# sch.net
KiCad netlist of a schematic drawn in Altium Designer
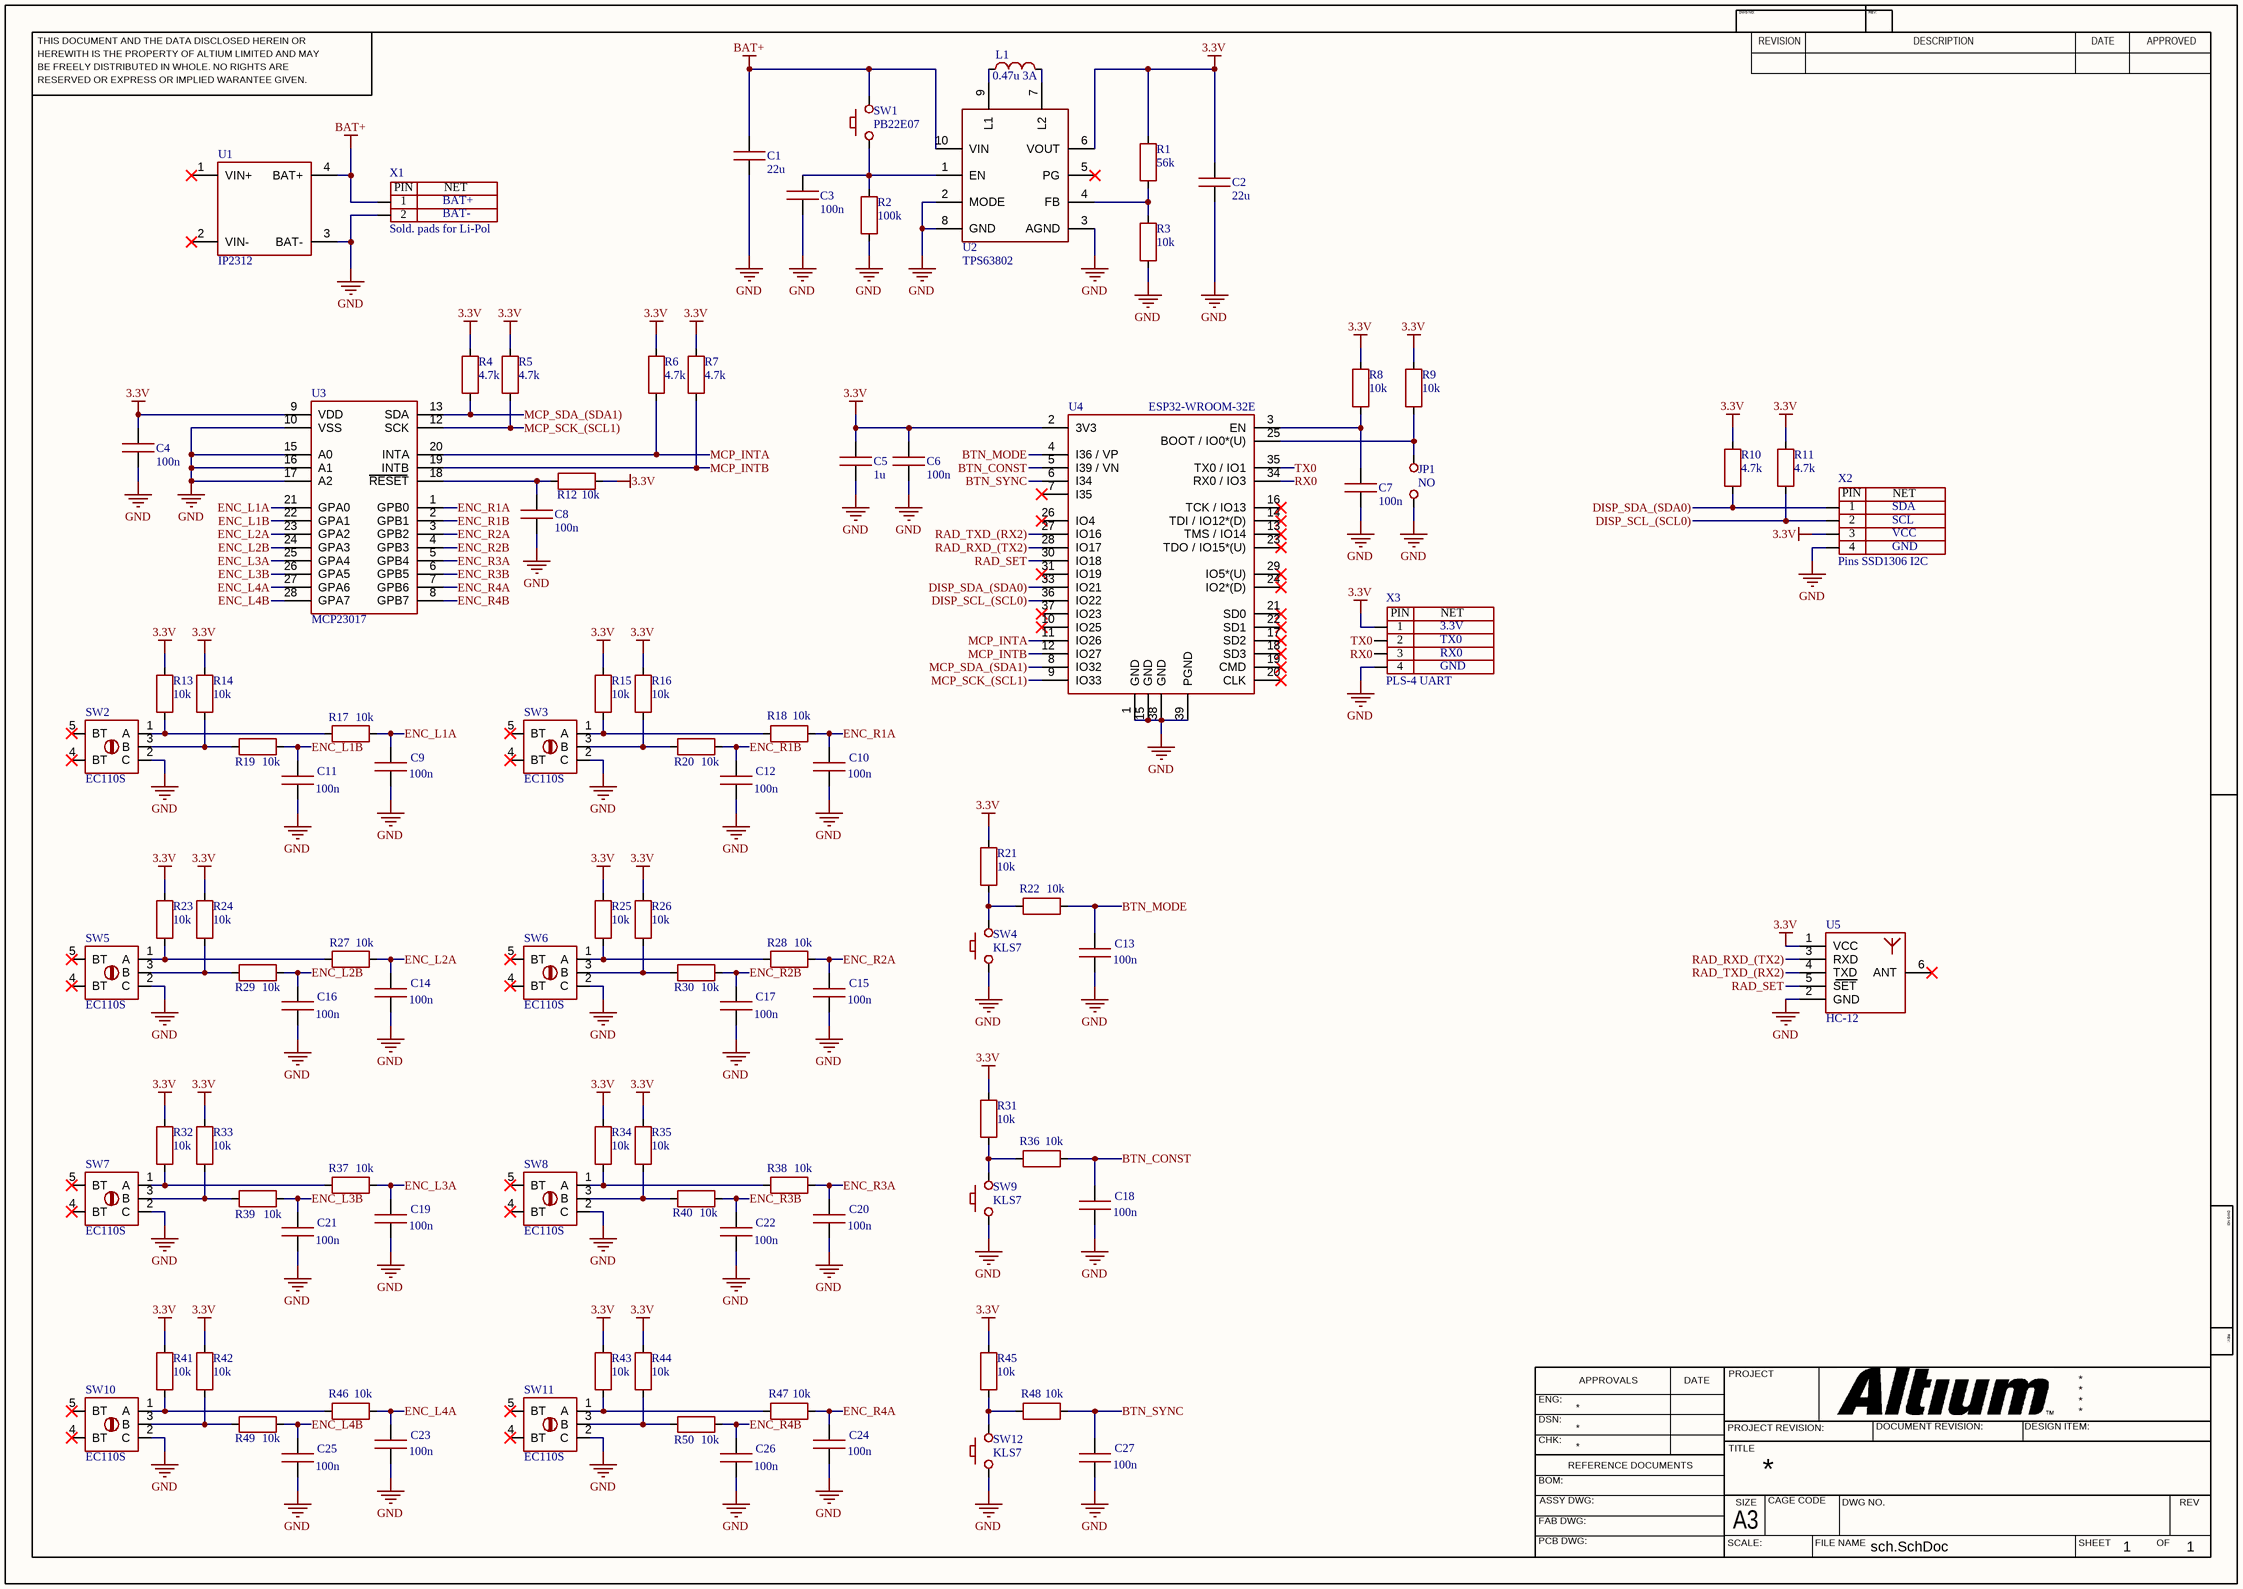
[diagram p0: sch.SchDoc]

(export (version "E")
  (design (tool "Eeschema 10.0.6"))
  (components
    (comp (ref "C1")
      (value "22u")
      (footprint "C1210")
      (description "22 мкФ X7R 10% 25В 1210, GRM32ER71E226KE15L")
      (libsource (lib "LeeSch") (part "Capacitor"))
    )
    (comp (ref "C2")
      (value "22u")
      (footprint "C1210")
      (description "22 мкФ X7R 10% 25В 1210, GRM32ER71E226KE15L")
      (libsource (lib "LeeSch") (part "Capacitor"))
    )
    (comp (ref "C3")
      (value "100n")
      (footprint "C0402")
      (description "0.1 мкФ X7R 25В 10% 0402, GRM155R71E104KE14D")
      (libsource (lib "LeeSch") (part "Capacitor"))
    )
    (comp (ref "C4")
      (value "100n")
      (footprint "C0402")
      (description "0.1 мкФ X7R 25В 10% 0402, GRM155R71E104KE14D")
      (libsource (lib "LeeSch") (part "Capacitor"))
    )
    (comp (ref "C5")
      (value "1u")
      (footprint "C0603")
      (description "1 мкФ X7R 25В 10% 0603, GCM188R71E105KA64D")
      (libsource (lib "LeeSch") (part "Capacitor"))
    )
    (comp (ref "C6")
      (value "100n")
      (footprint "C0402")
      (description "0.1 мкФ X7R 25В 10% 0402, GRM155R71E104KE14D")
      (libsource (lib "LeeSch") (part "Capacitor"))
    )
    (comp (ref "C7")
      (value "100n")
      (footprint "C0402")
      (description "0.1 мкФ X7R 25В 10% 0402, GRM155R71E104KE14D")
      (libsource (lib "LeeSch") (part "Capacitor"))
    )
    (comp (ref "C8")
      (value "100n")
      (footprint "C0402")
      (description "0.1 мкФ X7R 25В 10% 0402, GRM155R71E104KE14D")
      (libsource (lib "LeeSch") (part "Capacitor"))
    )
    (comp (ref "C9")
      (value "100n")
      (footprint "C0402")
      (description "0.1 мкФ X7R 25В 10% 0402, GRM155R71E104KE14D")
      (libsource (lib "LeeSch") (part "Capacitor"))
    )
    (comp (ref "C10")
      (value "100n")
      (footprint "C0402")
      (description "0.1 мкФ X7R 25В 10% 0402, GRM155R71E104KE14D")
      (libsource (lib "LeeSch") (part "Capacitor"))
    )
    (comp (ref "C11")
      (value "100n")
      (footprint "C0402")
      (description "0.1 мкФ X7R 25В 10% 0402, GRM155R71E104KE14D")
      (libsource (lib "LeeSch") (part "Capacitor"))
    )
    (comp (ref "C12")
      (value "100n")
      (footprint "C0402")
      (description "0.1 мкФ X7R 25В 10% 0402, GRM155R71E104KE14D")
      (libsource (lib "LeeSch") (part "Capacitor"))
    )
    (comp (ref "C13")
      (value "100n")
      (footprint "C0402")
      (description "0.1 мкФ X7R 25В 10% 0402, GRM155R71E104KE14D")
      (libsource (lib "LeeSch") (part "Capacitor"))
    )
    (comp (ref "C14")
      (value "100n")
      (footprint "C0402")
      (description "0.1 мкФ X7R 25В 10% 0402, GRM155R71E104KE14D")
      (libsource (lib "LeeSch") (part "Capacitor"))
    )
    (comp (ref "C15")
      (value "100n")
      (footprint "C0402")
      (description "0.1 мкФ X7R 25В 10% 0402, GRM155R71E104KE14D")
      (libsource (lib "LeeSch") (part "Capacitor"))
    )
    (comp (ref "C16")
      (value "100n")
      (footprint "C0402")
      (description "0.1 мкФ X7R 25В 10% 0402, GRM155R71E104KE14D")
      (libsource (lib "LeeSch") (part "Capacitor"))
    )
    (comp (ref "C17")
      (value "100n")
      (footprint "C0402")
      (description "0.1 мкФ X7R 25В 10% 0402, GRM155R71E104KE14D")
      (libsource (lib "LeeSch") (part "Capacitor"))
    )
    (comp (ref "C18")
      (value "100n")
      (footprint "C0402")
      (description "0.1 мкФ X7R 25В 10% 0402, GRM155R71E104KE14D")
      (libsource (lib "LeeSch") (part "Capacitor"))
    )
    (comp (ref "C19")
      (value "100n")
      (footprint "C0402")
      (description "0.1 мкФ X7R 25В 10% 0402, GRM155R71E104KE14D")
      (libsource (lib "LeeSch") (part "Capacitor"))
    )
    (comp (ref "C20")
      (value "100n")
      (footprint "C0402")
      (description "0.1 мкФ X7R 25В 10% 0402, GRM155R71E104KE14D")
      (libsource (lib "LeeSch") (part "Capacitor"))
    )
    (comp (ref "C21")
      (value "100n")
      (footprint "C0402")
      (description "0.1 мкФ X7R 25В 10% 0402, GRM155R71E104KE14D")
      (libsource (lib "LeeSch") (part "Capacitor"))
    )
    (comp (ref "C22")
      (value "100n")
      (footprint "C0402")
      (description "0.1 мкФ X7R 25В 10% 0402, GRM155R71E104KE14D")
      (libsource (lib "LeeSch") (part "Capacitor"))
    )
    (comp (ref "C23")
      (value "100n")
      (footprint "C0402")
      (description "0.1 мкФ X7R 25В 10% 0402, GRM155R71E104KE14D")
      (libsource (lib "LeeSch") (part "Capacitor"))
    )
    (comp (ref "C24")
      (value "100n")
      (footprint "C0402")
      (description "0.1 мкФ X7R 25В 10% 0402, GRM155R71E104KE14D")
      (libsource (lib "LeeSch") (part "Capacitor"))
    )
    (comp (ref "C25")
      (value "100n")
      (footprint "C0402")
      (description "0.1 мкФ X7R 25В 10% 0402, GRM155R71E104KE14D")
      (libsource (lib "LeeSch") (part "Capacitor"))
    )
    (comp (ref "C26")
      (value "100n")
      (footprint "C0402")
      (description "0.1 мкФ X7R 25В 10% 0402, GRM155R71E104KE14D")
      (libsource (lib "LeeSch") (part "Capacitor"))
    )
    (comp (ref "C27")
      (value "100n")
      (footprint "C0402")
      (description "0.1 мкФ X7R 25В 10% 0402, GRM155R71E104KE14D")
      (libsource (lib "LeeSch") (part "Capacitor"))
    )
    (comp (ref "JP1")
      (value "NO")
      (footprint "jumper 3mm")
      (libsource (lib "LeeSch") (part "Jumper (Normal Open)"))
    )
    (comp (ref "L1")
      (value "0.47u 3A")
      (footprint "INDUCTOR 2x1.6mm VLS-CX")
      (description "VLS201610CX-R47M-1, 0.47мкГн, 3.16А")
      (libsource (lib "LeeSch") (part "Inductance"))
    )
    (comp (ref "R1")
      (value "56k")
      (footprint "R0402")
      (description "0402")
      (libsource (lib "") (part "Resistor_2"))
    )
    (comp (ref "R2")
      (value "100k")
      (footprint "R0402")
      (description "0402")
      (libsource (lib "") (part "Resistor_2"))
    )
    (comp (ref "R3")
      (value "10k")
      (footprint "R0402")
      (description "0402")
      (libsource (lib "") (part "Resistor_2"))
    )
    (comp (ref "R4")
      (value "4.7k")
      (footprint "R0402")
      (description "0402")
      (libsource (lib "") (part "Resistor_2"))
    )
    (comp (ref "R5")
      (value "4.7k")
      (footprint "R0402")
      (description "0402")
      (libsource (lib "") (part "Resistor_2"))
    )
    (comp (ref "R6")
      (value "4.7k")
      (footprint "R0402")
      (description "0402")
      (libsource (lib "") (part "Resistor_2"))
    )
    (comp (ref "R7")
      (value "4.7k")
      (footprint "R0402")
      (description "0402")
      (libsource (lib "") (part "Resistor_2"))
    )
    (comp (ref "R8")
      (value "10k")
      (footprint "R0402")
      (description "0402")
      (libsource (lib "") (part "Resistor_2"))
    )
    (comp (ref "R9")
      (value "10k")
      (footprint "R0402")
      (description "0402")
      (libsource (lib "") (part "Resistor_2"))
    )
    (comp (ref "R10")
      (value "4.7k")
      (footprint "R0402")
      (description "0402")
      (libsource (lib "") (part "Resistor_2"))
    )
    (comp (ref "R11")
      (value "4.7k")
      (footprint "R0402")
      (description "0402")
      (libsource (lib "") (part "Resistor_2"))
    )
    (comp (ref "R12")
      (value "10k")
      (footprint "R0402")
      (description "0402")
      (libsource (lib "LeeSch") (part "Resistor"))
    )
    (comp (ref "R13")
      (value "10k")
      (footprint "R0402")
      (description "0402")
      (libsource (lib "LeeSch") (part "Resistor"))
    )
    (comp (ref "R14")
      (value "10k")
      (footprint "R0402")
      (description "0402")
      (libsource (lib "LeeSch") (part "Resistor"))
    )
    (comp (ref "R15")
      (value "10k")
      (footprint "R0402")
      (description "0402")
      (libsource (lib "LeeSch") (part "Resistor"))
    )
    (comp (ref "R16")
      (value "10k")
      (footprint "R0402")
      (description "0402")
      (libsource (lib "LeeSch") (part "Resistor"))
    )
    (comp (ref "R17")
      (value "10k")
      (footprint "R0402")
      (description "0402")
      (libsource (lib "") (part "Resistor_1"))
    )
    (comp (ref "R18")
      (value "10k")
      (footprint "R0402")
      (description "0402")
      (libsource (lib "") (part "Resistor_1"))
    )
    (comp (ref "R19")
      (value "10k")
      (footprint "R0402")
      (description "0402")
      (libsource (lib "") (part "Resistor_1"))
    )
    (comp (ref "R20")
      (value "10k")
      (footprint "R0402")
      (description "0402")
      (libsource (lib "") (part "Resistor_1"))
    )
    (comp (ref "R21")
      (value "10k")
      (footprint "R0402")
      (description "0402")
      (libsource (lib "") (part "Resistor_2"))
    )
    (comp (ref "R22")
      (value "10k")
      (footprint "R0402")
      (description "0402")
      (libsource (lib "") (part "Resistor_1"))
    )
    (comp (ref "R23")
      (value "10k")
      (footprint "R0402")
      (description "0402")
      (libsource (lib "LeeSch") (part "Resistor"))
    )
    (comp (ref "R24")
      (value "10k")
      (footprint "R0402")
      (description "0402")
      (libsource (lib "LeeSch") (part "Resistor"))
    )
    (comp (ref "R25")
      (value "10k")
      (footprint "R0402")
      (description "0402")
      (libsource (lib "LeeSch") (part "Resistor"))
    )
    (comp (ref "R26")
      (value "10k")
      (footprint "R0402")
      (description "0402")
      (libsource (lib "LeeSch") (part "Resistor"))
    )
    (comp (ref "R27")
      (value "10k")
      (footprint "R0402")
      (description "0402")
      (libsource (lib "") (part "Resistor_1"))
    )
    (comp (ref "R28")
      (value "10k")
      (footprint "R0402")
      (description "0402")
      (libsource (lib "") (part "Resistor_1"))
    )
    (comp (ref "R29")
      (value "10k")
      (footprint "R0402")
      (description "0402")
      (libsource (lib "") (part "Resistor_1"))
    )
    (comp (ref "R30")
      (value "10k")
      (footprint "R0402")
      (description "0402")
      (libsource (lib "") (part "Resistor_1"))
    )
    (comp (ref "R31")
      (value "10k")
      (footprint "R0402")
      (description "0402")
      (libsource (lib "") (part "Resistor_2"))
    )
    (comp (ref "R32")
      (value "10k")
      (footprint "R0402")
      (description "0402")
      (libsource (lib "LeeSch") (part "Resistor"))
    )
    (comp (ref "R33")
      (value "10k")
      (footprint "R0402")
      (description "0402")
      (libsource (lib "LeeSch") (part "Resistor"))
    )
    (comp (ref "R34")
      (value "10k")
      (footprint "R0402")
      (description "0402")
      (libsource (lib "LeeSch") (part "Resistor"))
    )
    (comp (ref "R35")
      (value "10k")
      (footprint "R0402")
      (description "0402")
      (libsource (lib "LeeSch") (part "Resistor"))
    )
    (comp (ref "R36")
      (value "10k")
      (footprint "R0402")
      (description "0402")
      (libsource (lib "") (part "Resistor_1"))
    )
    (comp (ref "R37")
      (value "10k")
      (footprint "R0402")
      (description "0402")
      (libsource (lib "") (part "Resistor_1"))
    )
    (comp (ref "R38")
      (value "10k")
      (footprint "R0402")
      (description "0402")
      (libsource (lib "") (part "Resistor_1"))
    )
    (comp (ref "R39")
      (value "10k")
      (footprint "R0402")
      (description "0402")
      (libsource (lib "") (part "Resistor_1"))
    )
    (comp (ref "R40")
      (value "10k")
      (footprint "R0402")
      (description "0402")
      (libsource (lib "") (part "Resistor_1"))
    )
    (comp (ref "R41")
      (value "10k")
      (footprint "R0402")
      (description "0402")
      (libsource (lib "LeeSch") (part "Resistor"))
    )
    (comp (ref "R42")
      (value "10k")
      (footprint "R0402")
      (description "0402")
      (libsource (lib "LeeSch") (part "Resistor"))
    )
    (comp (ref "R43")
      (value "10k")
      (footprint "R0402")
      (description "0402")
      (libsource (lib "LeeSch") (part "Resistor"))
    )
    (comp (ref "R44")
      (value "10k")
      (footprint "R0402")
      (description "0402")
      (libsource (lib "LeeSch") (part "Resistor"))
    )
    (comp (ref "R45")
      (value "10k")
      (footprint "R0402")
      (description "0402")
      (libsource (lib "") (part "Resistor_2"))
    )
    (comp (ref "R46")
      (value "10k")
      (footprint "R0402")
      (description "0402")
      (libsource (lib "") (part "Resistor_1"))
    )
    (comp (ref "R47")
      (value "10k")
      (footprint "R0402")
      (description "0402")
      (libsource (lib "") (part "Resistor_1"))
    )
    (comp (ref "R48")
      (value "10k")
      (footprint "R0402")
      (description "0402")
      (libsource (lib "") (part "Resistor_1"))
    )
    (comp (ref "R49")
      (value "10k")
      (footprint "R0402")
      (description "0402")
      (libsource (lib "") (part "Resistor_1"))
    )
    (comp (ref "R50")
      (value "10k")
      (footprint "R0402")
      (description "0402")
      (libsource (lib "") (part "Resistor_1"))
    )
    (comp (ref "SW1")
      (value "PB22E07")
      (footprint "PB22E07 7х7х12")
      (description "PB22E07 с фиксацией 7x7x12 mm")
      (libsource (lib "LeeSch") (part "Switch Button (Normal Open)"))
    )
    (comp (ref "SW2")
      (value "EC110S")
      (footprint "EC110S(ЭНКОДЕР)")
      (description "Incremental Encoder with button\r\nEC110S 20/20 10mm")
      (libsource (lib "LeeSch") (part "Encoder (Incremental, with Button)"))
    )
    (comp (ref "SW3")
      (value "EC110S")
      (footprint "EC110S(ЭНКОДЕР)")
      (description "Incremental Encoder with button\r\nEC110S 20/20 10mm")
      (libsource (lib "LeeSch") (part "Encoder (Incremental, with Button)"))
    )
    (comp (ref "SW4")
      (value "KLS7")
      (footprint "SMT Tactile Switch (6mm x 6mm)")
      (description "KLS7-TS6604-4.3-180 (IT-1102S) 6х6х4.3мм")
      (libsource (lib "LeeSch") (part "Switch Button (Normal Open)"))
    )
    (comp (ref "SW5")
      (value "EC110S")
      (footprint "EC110S(ЭНКОДЕР)")
      (description "Incremental Encoder with button\r\nEC110S 20/20 10mm")
      (libsource (lib "LeeSch") (part "Encoder (Incremental, with Button)"))
    )
    (comp (ref "SW6")
      (value "EC110S")
      (footprint "EC110S(ЭНКОДЕР)")
      (description "Incremental Encoder with button\r\nEC110S 20/20 10mm")
      (libsource (lib "LeeSch") (part "Encoder (Incremental, with Button)"))
    )
    (comp (ref "SW7")
      (value "EC110S")
      (footprint "EC110S(ЭНКОДЕР)")
      (description "Incremental Encoder with button\r\nEC110S 20/20 10mm")
      (libsource (lib "LeeSch") (part "Encoder (Incremental, with Button)"))
    )
    (comp (ref "SW8")
      (value "EC110S")
      (footprint "EC110S(ЭНКОДЕР)")
      (description "Incremental Encoder with button\r\nEC110S 20/20 10mm")
      (libsource (lib "LeeSch") (part "Encoder (Incremental, with Button)"))
    )
    (comp (ref "SW9")
      (value "KLS7")
      (footprint "SMT Tactile Switch (6mm x 6mm)")
      (description "KLS7-TS6604-4.3-180 (IT-1102S) 6х6х4.3мм")
      (libsource (lib "LeeSch") (part "Switch Button (Normal Open)"))
    )
    (comp (ref "SW10")
      (value "EC110S")
      (footprint "EC110S(ЭНКОДЕР)")
      (description "Incremental Encoder with button\r\nEC110S 20/20 10mm")
      (libsource (lib "LeeSch") (part "Encoder (Incremental, with Button)"))
    )
    (comp (ref "SW11")
      (value "EC110S")
      (footprint "EC110S(ЭНКОДЕР)")
      (description "Incremental Encoder with button\r\nEC110S 20/20 10mm")
      (libsource (lib "LeeSch") (part "Encoder (Incremental, with Button)"))
    )
    (comp (ref "SW12")
      (value "KLS7")
      (footprint "SMT Tactile Switch (6mm x 6mm)")
      (description "KLS7-TS6604-4.3-180 (IT-1102S) 6х6х4.3мм")
      (libsource (lib "LeeSch") (part "Switch Button (Normal Open)"))
    )
    (comp (ref "U1")
      (value "IP2312")
      (footprint "IP2312 Modul")
      (description "Impulse charger without protection")
      (libsource (lib "LeeSch") (part "MOD_Charger_IP2312"))
    )
    (comp (ref "U2")
      (value "TPS63802")
      (footprint "VSON-HR-10(3x2)")
      (description "Integral Buck-Boost Regulator 2A out")
      (libsource (lib "LeeSch") (part "IC_ImpRegulator_TPS63802"))
    )
    (comp (ref "U3")
      (value "MCP23017")
      (footprint "SSOP-28N")
      (description "16-Bit I/O Expander with Serial Interface")
      (libsource (lib "LeeSch") (part "IC_PortsExp_MCP23017"))
    )
    (comp (ref "U4")
      (value "ESP32-WROOM-32E")
      (footprint "ESP32­WROOM­32E")
      (libsource (lib "LeeSch") (part "MOD_ESP32-WROOM-32"))
    )
    (comp (ref "U5")
      (value "HC-12")
      (footprint "HC-12(Модуль)")
      (description "Radio module 433MHz UART Interface")
      (libsource (lib "LeeSch") (part "MOD_RadioMod_HC-12"))
    )
    (comp (ref "X1")
      (value "Sold. pads for Li-Pol")
      (footprint "CWF-2R (DS1069-2 MR)")
      (libsource (lib "LeeSch") (part "Terminal block (2-pin)"))
    )
    (comp (ref "X2")
      (value "Pins SSD1306 I2C")
      (footprint "SSD1306 27.5x27.8 NO GABARIT")
      (libsource (lib "LeeSch") (part "Terminal block (4-pin)"))
    )
    (comp (ref "X3")
      (value "PLS-4 UART")
      (footprint "PLS-4")
      (libsource (lib "LeeSch") (part "Terminal block (4-pin)"))
    )
  )
  (nets
    (net (code "1") (name "/BTN_CONST") (class "Default")
      (node (ref "C18") (pin "2") (pinfunction "2_2") (pintype "passive"))
      (node (ref "R36") (pin "1") (pinfunction "1_1") (pintype "passive"))
      (node (ref "U4") (pin "5") (pinfunction "I39_/_VN_5") (pintype "passive"))
    )
    (net (code "2") (name "/BTN_MODE") (class "Default")
      (node (ref "C13") (pin "2") (pinfunction "2_2") (pintype "passive"))
      (node (ref "R22") (pin "1") (pinfunction "1_1") (pintype "passive"))
      (node (ref "U4") (pin "4") (pinfunction "I36_/_VP_4") (pintype "passive"))
    )
    (net (code "3") (name "/BTN_SYNC") (class "Default")
      (node (ref "C27") (pin "2") (pinfunction "2_2") (pintype "passive"))
      (node (ref "R48") (pin "1") (pinfunction "1_1") (pintype "passive"))
      (node (ref "U4") (pin "6") (pinfunction "I34_6") (pintype "passive"))
    )
    (net (code "4") (name "/DISP_SCL_(SCL0)") (class "Default")
      (node (ref "R11") (pin "1") (pinfunction "1_1") (pintype "passive"))
      (node (ref "U4") (pin "36") (pinfunction "IO22_36") (pintype "passive"))
      (node (ref "X2") (pin "2") (pinfunction "NET2_2") (pintype "passive"))
    )
    (net (code "5") (name "/DISP_SDA_(SDA0)") (class "Default")
      (node (ref "R10") (pin "1") (pinfunction "1_1") (pintype "passive"))
      (node (ref "U4") (pin "33") (pinfunction "IO21_33") (pintype "passive"))
      (node (ref "X2") (pin "1") (pinfunction "NET1_1") (pintype "passive"))
    )
    (net (code "6") (name "/ENC_L1A") (class "Default")
      (node (ref "C9") (pin "2") (pinfunction "2_2") (pintype "passive"))
      (node (ref "R17") (pin "1") (pinfunction "1_1") (pintype "passive"))
      (node (ref "U3") (pin "21") (pinfunction "GPA0_21") (pintype "passive"))
    )
    (net (code "7") (name "/ENC_L1B") (class "Default")
      (node (ref "C11") (pin "2") (pinfunction "2_2") (pintype "passive"))
      (node (ref "R19") (pin "1") (pinfunction "1_1") (pintype "passive"))
      (node (ref "U3") (pin "22") (pinfunction "GPA1_22") (pintype "passive"))
    )
    (net (code "8") (name "/ENC_L2A") (class "Default")
      (node (ref "C14") (pin "2") (pinfunction "2_2") (pintype "passive"))
      (node (ref "R27") (pin "1") (pinfunction "1_1") (pintype "passive"))
      (node (ref "U3") (pin "23") (pinfunction "GPA2_23") (pintype "passive"))
    )
    (net (code "9") (name "/ENC_L2B") (class "Default")
      (node (ref "C16") (pin "2") (pinfunction "2_2") (pintype "passive"))
      (node (ref "R29") (pin "1") (pinfunction "1_1") (pintype "passive"))
      (node (ref "U3") (pin "24") (pinfunction "GPA3_24") (pintype "passive"))
    )
    (net (code "10") (name "/ENC_L3A") (class "Default")
      (node (ref "C19") (pin "2") (pinfunction "2_2") (pintype "passive"))
      (node (ref "R37") (pin "1") (pinfunction "1_1") (pintype "passive"))
      (node (ref "U3") (pin "25") (pinfunction "GPA4_25") (pintype "passive"))
    )
    (net (code "11") (name "/ENC_L3B") (class "Default")
      (node (ref "C21") (pin "2") (pinfunction "2_2") (pintype "passive"))
      (node (ref "R39") (pin "1") (pinfunction "1_1") (pintype "passive"))
      (node (ref "U3") (pin "26") (pinfunction "GPA5_26") (pintype "passive"))
    )
    (net (code "12") (name "/ENC_L4A") (class "Default")
      (node (ref "C23") (pin "2") (pinfunction "2_2") (pintype "passive"))
      (node (ref "R46") (pin "1") (pinfunction "1_1") (pintype "passive"))
      (node (ref "U3") (pin "27") (pinfunction "GPA6_27") (pintype "passive"))
    )
    (net (code "13") (name "/ENC_L4B") (class "Default")
      (node (ref "C25") (pin "2") (pinfunction "2_2") (pintype "passive"))
      (node (ref "R49") (pin "1") (pinfunction "1_1") (pintype "passive"))
      (node (ref "U3") (pin "28") (pinfunction "GPA7_28") (pintype "passive"))
    )
    (net (code "14") (name "/ENC_R1A") (class "Default")
      (node (ref "C10") (pin "2") (pinfunction "2_2") (pintype "passive"))
      (node (ref "R18") (pin "1") (pinfunction "1_1") (pintype "passive"))
      (node (ref "U3") (pin "1") (pinfunction "GPB0_1") (pintype "passive"))
    )
    (net (code "15") (name "/ENC_R1B") (class "Default")
      (node (ref "C12") (pin "2") (pinfunction "2_2") (pintype "passive"))
      (node (ref "R20") (pin "1") (pinfunction "1_1") (pintype "passive"))
      (node (ref "U3") (pin "2") (pinfunction "GPB1_2") (pintype "passive"))
    )
    (net (code "16") (name "/ENC_R2A") (class "Default")
      (node (ref "C15") (pin "2") (pinfunction "2_2") (pintype "passive"))
      (node (ref "R28") (pin "1") (pinfunction "1_1") (pintype "passive"))
      (node (ref "U3") (pin "3") (pinfunction "GPB2_3") (pintype "passive"))
    )
    (net (code "17") (name "/ENC_R2B") (class "Default")
      (node (ref "C17") (pin "2") (pinfunction "2_2") (pintype "passive"))
      (node (ref "R30") (pin "1") (pinfunction "1_1") (pintype "passive"))
      (node (ref "U3") (pin "4") (pinfunction "GPB3_4") (pintype "passive"))
    )
    (net (code "18") (name "/ENC_R3A") (class "Default")
      (node (ref "C20") (pin "2") (pinfunction "2_2") (pintype "passive"))
      (node (ref "R38") (pin "1") (pinfunction "1_1") (pintype "passive"))
      (node (ref "U3") (pin "5") (pinfunction "GPB4_5") (pintype "passive"))
    )
    (net (code "19") (name "/ENC_R3B") (class "Default")
      (node (ref "C22") (pin "2") (pinfunction "2_2") (pintype "passive"))
      (node (ref "R40") (pin "1") (pinfunction "1_1") (pintype "passive"))
      (node (ref "U3") (pin "6") (pinfunction "GPB5_6") (pintype "passive"))
    )
    (net (code "20") (name "/ENC_R4A") (class "Default")
      (node (ref "C24") (pin "2") (pinfunction "2_2") (pintype "passive"))
      (node (ref "R47") (pin "1") (pinfunction "1_1") (pintype "passive"))
      (node (ref "U3") (pin "7") (pinfunction "GPB6_7") (pintype "passive"))
    )
    (net (code "21") (name "/ENC_R4B") (class "Default")
      (node (ref "C26") (pin "2") (pinfunction "2_2") (pintype "passive"))
      (node (ref "R50") (pin "1") (pinfunction "1_1") (pintype "passive"))
      (node (ref "U3") (pin "8") (pinfunction "GPB7_8") (pintype "passive"))
    )
    (net (code "22") (name "/MCP_INTA") (class "Default")
      (node (ref "R6") (pin "1") (pinfunction "1_1") (pintype "passive"))
      (node (ref "U3") (pin "20") (pinfunction "INTA_20") (pintype "passive"))
      (node (ref "U4") (pin "11") (pinfunction "IO26_11") (pintype "passive"))
    )
    (net (code "23") (name "/MCP_INTB") (class "Default")
      (node (ref "R7") (pin "1") (pinfunction "1_1") (pintype "passive"))
      (node (ref "U3") (pin "19") (pinfunction "INTB_19") (pintype "passive"))
      (node (ref "U4") (pin "12") (pinfunction "IO27_12") (pintype "passive"))
    )
    (net (code "24") (name "/MCP_SCK_(SCL1)") (class "Default")
      (node (ref "R5") (pin "1") (pinfunction "1_1") (pintype "passive"))
      (node (ref "U3") (pin "12") (pinfunction "SCK_12") (pintype "passive"))
      (node (ref "U4") (pin "9") (pinfunction "IO33_9") (pintype "passive"))
    )
    (net (code "25") (name "/MCP_SDA_(SDA1)") (class "Default")
      (node (ref "R4") (pin "1") (pinfunction "1_1") (pintype "passive"))
      (node (ref "U3") (pin "13") (pinfunction "SDA_13") (pintype "passive"))
      (node (ref "U4") (pin "8") (pinfunction "IO32_8") (pintype "passive"))
    )
    (net (code "26") (name "/RAD_RXD_(TX2)") (class "Default")
      (node (ref "U4") (pin "28") (pinfunction "IO17_28") (pintype "passive"))
      (node (ref "U5") (pin "3") (pinfunction "RXD_3") (pintype "passive"))
    )
    (net (code "27") (name "/RAD_SET") (class "Default")
      (node (ref "U4") (pin "30") (pinfunction "IO18_30") (pintype "passive"))
      (node (ref "U5") (pin "5") (pinfunction "SET_5") (pintype "passive"))
    )
    (net (code "28") (name "/RAD_TXD_(RX2)") (class "Default")
      (node (ref "U4") (pin "27") (pinfunction "IO16_27") (pintype "passive"))
      (node (ref "U5") (pin "4") (pinfunction "TXD_4") (pintype "passive"))
    )
    (net (code "29") (name "/RX0") (class "Default")
      (node (ref "U4") (pin "34") (pinfunction "RX0_/_IO3_34") (pintype "passive"))
      (node (ref "X3") (pin "3") (pinfunction "NET3_3") (pintype "passive"))
    )
    (net (code "30") (name "/TX0") (class "Default")
      (node (ref "U4") (pin "35") (pinfunction "TX0_/_IO1_35") (pintype "passive"))
      (node (ref "X3") (pin "2") (pinfunction "NET2_2") (pintype "passive"))
    )
    (net (code "31") (name "3.3V") (class "Default")
      (node (ref "C2") (pin "2") (pinfunction "2_2") (pintype "passive"))
      (node (ref "C4") (pin "2") (pinfunction "2_2") (pintype "passive"))
      (node (ref "C5") (pin "2") (pinfunction "2_2") (pintype "passive"))
      (node (ref "C6") (pin "2") (pinfunction "2_2") (pintype "passive"))
      (node (ref "R1") (pin "2") (pinfunction "2_2") (pintype "passive"))
      (node (ref "R10") (pin "2") (pinfunction "2_2") (pintype "passive"))
      (node (ref "R11") (pin "2") (pinfunction "2_2") (pintype "passive"))
      (node (ref "R12") (pin "1") (pinfunction "1_1") (pintype "passive"))
      (node (ref "R13") (pin "1") (pinfunction "1_1") (pintype "passive"))
      (node (ref "R14") (pin "1") (pinfunction "1_1") (pintype "passive"))
      (node (ref "R15") (pin "1") (pinfunction "1_1") (pintype "passive"))
      (node (ref "R16") (pin "1") (pinfunction "1_1") (pintype "passive"))
      (node (ref "R21") (pin "2") (pinfunction "2_2") (pintype "passive"))
      (node (ref "R23") (pin "1") (pinfunction "1_1") (pintype "passive"))
      (node (ref "R24") (pin "1") (pinfunction "1_1") (pintype "passive"))
      (node (ref "R25") (pin "1") (pinfunction "1_1") (pintype "passive"))
      (node (ref "R26") (pin "1") (pinfunction "1_1") (pintype "passive"))
      (node (ref "R31") (pin "2") (pinfunction "2_2") (pintype "passive"))
      (node (ref "R32") (pin "1") (pinfunction "1_1") (pintype "passive"))
      (node (ref "R33") (pin "1") (pinfunction "1_1") (pintype "passive"))
      (node (ref "R34") (pin "1") (pinfunction "1_1") (pintype "passive"))
      (node (ref "R35") (pin "1") (pinfunction "1_1") (pintype "passive"))
      (node (ref "R4") (pin "2") (pinfunction "2_2") (pintype "passive"))
      (node (ref "R41") (pin "1") (pinfunction "1_1") (pintype "passive"))
      (node (ref "R42") (pin "1") (pinfunction "1_1") (pintype "passive"))
      (node (ref "R43") (pin "1") (pinfunction "1_1") (pintype "passive"))
      (node (ref "R44") (pin "1") (pinfunction "1_1") (pintype "passive"))
      (node (ref "R45") (pin "2") (pinfunction "2_2") (pintype "passive"))
      (node (ref "R5") (pin "2") (pinfunction "2_2") (pintype "passive"))
      (node (ref "R6") (pin "2") (pinfunction "2_2") (pintype "passive"))
      (node (ref "R7") (pin "2") (pinfunction "2_2") (pintype "passive"))
      (node (ref "R8") (pin "2") (pinfunction "2_2") (pintype "passive"))
      (node (ref "R9") (pin "2") (pinfunction "2_2") (pintype "passive"))
      (node (ref "U2") (pin "6") (pinfunction "VOUT_6") (pintype "power_in"))
      (node (ref "U3") (pin "9") (pinfunction "VDD_9") (pintype "power_in"))
      (node (ref "U4") (pin "2") (pinfunction "3V3_2") (pintype "power_in"))
      (node (ref "U5") (pin "1") (pinfunction "VCC_1") (pintype "power_in"))
      (node (ref "X2") (pin "3") (pinfunction "NET3_3") (pintype "passive"))
      (node (ref "X3") (pin "1") (pinfunction "NET1_1") (pintype "passive"))
    )
    (net (code "32") (name "BAT+") (class "Default")
      (node (ref "C1") (pin "2") (pinfunction "2_2") (pintype "passive"))
      (node (ref "SW1") (pin "2") (pinfunction "2_2") (pintype "passive"))
      (node (ref "U1") (pin "4") (pinfunction "BAT+_4") (pintype "passive"))
      (node (ref "U2") (pin "10") (pinfunction "VIN_10") (pintype "power_in"))
      (node (ref "X1") (pin "1") (pinfunction "NET1_1") (pintype "passive"))
    )
    (net (code "33") (name "GND") (class "Default")
      (node (ref "C1") (pin "1") (pinfunction "1_1") (pintype "passive"))
      (node (ref "C10") (pin "1") (pinfunction "1_1") (pintype "passive"))
      (node (ref "C11") (pin "1") (pinfunction "1_1") (pintype "passive"))
      (node (ref "C12") (pin "1") (pinfunction "1_1") (pintype "passive"))
      (node (ref "C13") (pin "1") (pinfunction "1_1") (pintype "passive"))
      (node (ref "C14") (pin "1") (pinfunction "1_1") (pintype "passive"))
      (node (ref "C15") (pin "1") (pinfunction "1_1") (pintype "passive"))
      (node (ref "C16") (pin "1") (pinfunction "1_1") (pintype "passive"))
      (node (ref "C17") (pin "1") (pinfunction "1_1") (pintype "passive"))
      (node (ref "C18") (pin "1") (pinfunction "1_1") (pintype "passive"))
      (node (ref "C19") (pin "1") (pinfunction "1_1") (pintype "passive"))
      (node (ref "C2") (pin "1") (pinfunction "1_1") (pintype "passive"))
      (node (ref "C20") (pin "1") (pinfunction "1_1") (pintype "passive"))
      (node (ref "C21") (pin "1") (pinfunction "1_1") (pintype "passive"))
      (node (ref "C22") (pin "1") (pinfunction "1_1") (pintype "passive"))
      (node (ref "C23") (pin "1") (pinfunction "1_1") (pintype "passive"))
      (node (ref "C24") (pin "1") (pinfunction "1_1") (pintype "passive"))
      (node (ref "C25") (pin "1") (pinfunction "1_1") (pintype "passive"))
      (node (ref "C26") (pin "1") (pinfunction "1_1") (pintype "passive"))
      (node (ref "C27") (pin "1") (pinfunction "1_1") (pintype "passive"))
      (node (ref "C3") (pin "1") (pinfunction "1_1") (pintype "passive"))
      (node (ref "C4") (pin "1") (pinfunction "1_1") (pintype "passive"))
      (node (ref "C5") (pin "1") (pinfunction "1_1") (pintype "passive"))
      (node (ref "C6") (pin "1") (pinfunction "1_1") (pintype "passive"))
      (node (ref "C7") (pin "1") (pinfunction "1_1") (pintype "passive"))
      (node (ref "C8") (pin "1") (pinfunction "1_1") (pintype "passive"))
      (node (ref "C9") (pin "1") (pinfunction "1_1") (pintype "passive"))
      (node (ref "JP1") (pin "1") (pinfunction "1_1") (pintype "passive"))
      (node (ref "R2") (pin "1") (pinfunction "1_1") (pintype "passive"))
      (node (ref "R3") (pin "1") (pinfunction "1_1") (pintype "passive"))
      (node (ref "SW10") (pin "2") (pinfunction "C_2") (pintype "passive"))
      (node (ref "SW11") (pin "2") (pinfunction "C_2") (pintype "passive"))
      (node (ref "SW12") (pin "1") (pinfunction "1_1") (pintype "passive"))
      (node (ref "SW2") (pin "2") (pinfunction "C_2") (pintype "passive"))
      (node (ref "SW3") (pin "2") (pinfunction "C_2") (pintype "passive"))
      (node (ref "SW4") (pin "1") (pinfunction "1_1") (pintype "passive"))
      (node (ref "SW5") (pin "2") (pinfunction "C_2") (pintype "passive"))
      (node (ref "SW6") (pin "2") (pinfunction "C_2") (pintype "passive"))
      (node (ref "SW7") (pin "2") (pinfunction "C_2") (pintype "passive"))
      (node (ref "SW8") (pin "2") (pinfunction "C_2") (pintype "passive"))
      (node (ref "SW9") (pin "1") (pinfunction "1_1") (pintype "passive"))
      (node (ref "U1") (pin "3") (pinfunction "BAT-_3") (pintype "passive"))
      (node (ref "U2") (pin "2") (pinfunction "MODE_2") (pintype "passive"))
      (node (ref "U2") (pin "3") (pinfunction "AGND_3") (pintype "power_in"))
      (node (ref "U2") (pin "8") (pinfunction "GND_8") (pintype "power_in"))
      (node (ref "U3") (pin "10") (pinfunction "VSS_10") (pintype "power_in"))
      (node (ref "U3") (pin "15") (pinfunction "A0_15") (pintype "passive"))
      (node (ref "U3") (pin "16") (pinfunction "A1_16") (pintype "passive"))
      (node (ref "U3") (pin "17") (pinfunction "A2_17") (pintype "passive"))
      (node (ref "U4") (pin "1") (pinfunction "GND_1") (pintype "power_in"))
      (node (ref "U4") (pin "15") (pinfunction "GND_15") (pintype "power_in"))
      (node (ref "U4") (pin "38") (pinfunction "GND_38") (pintype "power_in"))
      (node (ref "U4") (pin "39") (pinfunction "PGND_39") (pintype "power_in"))
      (node (ref "U5") (pin "2") (pinfunction "GND_2") (pintype "power_in"))
      (node (ref "X1") (pin "2") (pinfunction "NET2_2") (pintype "passive"))
      (node (ref "X2") (pin "4") (pinfunction "NET4_4") (pintype "passive"))
      (node (ref "X3") (pin "4") (pinfunction "NET4_4") (pintype "passive"))
    )
    (net (code "34") (name "Net-(R21-Pad1)") (class "Default")
      (node (ref "R21") (pin "1") (pinfunction "1_1") (pintype "passive"))
      (node (ref "R22") (pin "2") (pinfunction "2_2") (pintype "passive"))
      (node (ref "SW4") (pin "2") (pinfunction "2_2") (pintype "passive"))
    )
    (net (code "35") (name "Net-(R31-Pad1)") (class "Default")
      (node (ref "R31") (pin "1") (pinfunction "1_1") (pintype "passive"))
      (node (ref "R36") (pin "2") (pinfunction "2_2") (pintype "passive"))
      (node (ref "SW9") (pin "2") (pinfunction "2_2") (pintype "passive"))
    )
    (net (code "36") (name "Net-(R45-Pad1)") (class "Default")
      (node (ref "R45") (pin "1") (pinfunction "1_1") (pintype "passive"))
      (node (ref "R48") (pin "2") (pinfunction "2_2") (pintype "passive"))
      (node (ref "SW12") (pin "2") (pinfunction "2_2") (pintype "passive"))
    )
    (net (code "37") (name "Net-(SW2-A)") (class "Default")
      (node (ref "R13") (pin "2") (pinfunction "2_2") (pintype "passive"))
      (node (ref "R17") (pin "2") (pinfunction "2_2") (pintype "passive"))
      (node (ref "SW2") (pin "1") (pinfunction "A_1") (pintype "passive"))
    )
    (net (code "38") (name "Net-(SW2-B)") (class "Default")
      (node (ref "R14") (pin "2") (pinfunction "2_2") (pintype "passive"))
      (node (ref "R19") (pin "2") (pinfunction "2_2") (pintype "passive"))
      (node (ref "SW2") (pin "3") (pinfunction "B_3") (pintype "passive"))
    )
    (net (code "39") (name "Net-(SW3-A)") (class "Default")
      (node (ref "R15") (pin "2") (pinfunction "2_2") (pintype "passive"))
      (node (ref "R18") (pin "2") (pinfunction "2_2") (pintype "passive"))
      (node (ref "SW3") (pin "1") (pinfunction "A_1") (pintype "passive"))
    )
    (net (code "40") (name "Net-(SW3-B)") (class "Default")
      (node (ref "R16") (pin "2") (pinfunction "2_2") (pintype "passive"))
      (node (ref "R20") (pin "2") (pinfunction "2_2") (pintype "passive"))
      (node (ref "SW3") (pin "3") (pinfunction "B_3") (pintype "passive"))
    )
    (net (code "41") (name "Net-(SW5-A)") (class "Default")
      (node (ref "R23") (pin "2") (pinfunction "2_2") (pintype "passive"))
      (node (ref "R27") (pin "2") (pinfunction "2_2") (pintype "passive"))
      (node (ref "SW5") (pin "1") (pinfunction "A_1") (pintype "passive"))
    )
    (net (code "42") (name "Net-(SW5-B)") (class "Default")
      (node (ref "R24") (pin "2") (pinfunction "2_2") (pintype "passive"))
      (node (ref "R29") (pin "2") (pinfunction "2_2") (pintype "passive"))
      (node (ref "SW5") (pin "3") (pinfunction "B_3") (pintype "passive"))
    )
    (net (code "43") (name "Net-(SW6-A)") (class "Default")
      (node (ref "R25") (pin "2") (pinfunction "2_2") (pintype "passive"))
      (node (ref "R28") (pin "2") (pinfunction "2_2") (pintype "passive"))
      (node (ref "SW6") (pin "1") (pinfunction "A_1") (pintype "passive"))
    )
    (net (code "44") (name "Net-(SW6-B)") (class "Default")
      (node (ref "R26") (pin "2") (pinfunction "2_2") (pintype "passive"))
      (node (ref "R30") (pin "2") (pinfunction "2_2") (pintype "passive"))
      (node (ref "SW6") (pin "3") (pinfunction "B_3") (pintype "passive"))
    )
    (net (code "45") (name "Net-(SW7-A)") (class "Default")
      (node (ref "R32") (pin "2") (pinfunction "2_2") (pintype "passive"))
      (node (ref "R37") (pin "2") (pinfunction "2_2") (pintype "passive"))
      (node (ref "SW7") (pin "1") (pinfunction "A_1") (pintype "passive"))
    )
    (net (code "46") (name "Net-(SW7-B)") (class "Default")
      (node (ref "R33") (pin "2") (pinfunction "2_2") (pintype "passive"))
      (node (ref "R39") (pin "2") (pinfunction "2_2") (pintype "passive"))
      (node (ref "SW7") (pin "3") (pinfunction "B_3") (pintype "passive"))
    )
    (net (code "47") (name "Net-(SW8-A)") (class "Default")
      (node (ref "R34") (pin "2") (pinfunction "2_2") (pintype "passive"))
      (node (ref "R38") (pin "2") (pinfunction "2_2") (pintype "passive"))
      (node (ref "SW8") (pin "1") (pinfunction "A_1") (pintype "passive"))
    )
    (net (code "48") (name "Net-(SW8-B)") (class "Default")
      (node (ref "R35") (pin "2") (pinfunction "2_2") (pintype "passive"))
      (node (ref "R40") (pin "2") (pinfunction "2_2") (pintype "passive"))
      (node (ref "SW8") (pin "3") (pinfunction "B_3") (pintype "passive"))
    )
    (net (code "49") (name "Net-(SW10-A)") (class "Default")
      (node (ref "R41") (pin "2") (pinfunction "2_2") (pintype "passive"))
      (node (ref "R46") (pin "2") (pinfunction "2_2") (pintype "passive"))
      (node (ref "SW10") (pin "1") (pinfunction "A_1") (pintype "passive"))
    )
    (net (code "50") (name "Net-(SW10-B)") (class "Default")
      (node (ref "R42") (pin "2") (pinfunction "2_2") (pintype "passive"))
      (node (ref "R49") (pin "2") (pinfunction "2_2") (pintype "passive"))
      (node (ref "SW10") (pin "3") (pinfunction "B_3") (pintype "passive"))
    )
    (net (code "51") (name "Net-(SW11-A)") (class "Default")
      (node (ref "R43") (pin "2") (pinfunction "2_2") (pintype "passive"))
      (node (ref "R47") (pin "2") (pinfunction "2_2") (pintype "passive"))
      (node (ref "SW11") (pin "1") (pinfunction "A_1") (pintype "passive"))
    )
    (net (code "52") (name "Net-(SW11-B)") (class "Default")
      (node (ref "R44") (pin "2") (pinfunction "2_2") (pintype "passive"))
      (node (ref "R50") (pin "2") (pinfunction "2_2") (pintype "passive"))
      (node (ref "SW11") (pin "3") (pinfunction "B_3") (pintype "passive"))
    )
    (net (code "53") (name "Net-(U2-EN)") (class "Default")
      (node (ref "C3") (pin "2") (pinfunction "2_2") (pintype "passive"))
      (node (ref "R2") (pin "2") (pinfunction "2_2") (pintype "passive"))
      (node (ref "SW1") (pin "1") (pinfunction "1_1") (pintype "passive"))
      (node (ref "U2") (pin "1") (pinfunction "EN_1") (pintype "passive"))
    )
    (net (code "54") (name "Net-(U2-FB)") (class "Default")
      (node (ref "R1") (pin "1") (pinfunction "1_1") (pintype "passive"))
      (node (ref "R3") (pin "2") (pinfunction "2_2") (pintype "passive"))
      (node (ref "U2") (pin "4") (pinfunction "FB_4") (pintype "passive"))
    )
    (net (code "55") (name "Net-(U2-L1)") (class "Default")
      (node (ref "L1") (pin "1") (pinfunction "1_1") (pintype "passive"))
      (node (ref "U2") (pin "9") (pinfunction "L1_9") (pintype "passive"))
    )
    (net (code "56") (name "Net-(U2-L2)") (class "Default")
      (node (ref "L1") (pin "2") (pinfunction "2_2") (pintype "passive"))
      (node (ref "U2") (pin "7") (pinfunction "L2_7") (pintype "passive"))
    )
    (net (code "57") (name "Net-(U3-RESET)") (class "Default")
      (node (ref "C8") (pin "2") (pinfunction "2_2") (pintype "passive"))
      (node (ref "R12") (pin "2") (pinfunction "2_2") (pintype "passive"))
      (node (ref "U3") (pin "18") (pinfunction "RESET_18") (pintype "passive"))
    )
    (net (code "58") (name "Net-(U4-BOOT_{slash}_IO0*(U))") (class "Default")
      (node (ref "JP1") (pin "2") (pinfunction "2_2") (pintype "passive"))
      (node (ref "R9") (pin "1") (pinfunction "1_1") (pintype "passive"))
      (node (ref "U4") (pin "25") (pinfunction "BOOT_/_IO0*(U)_25") (pintype "passive"))
    )
    (net (code "59") (name "Net-(U4-EN)") (class "Default")
      (node (ref "C7") (pin "2") (pinfunction "2_2") (pintype "passive"))
      (node (ref "R8") (pin "1") (pinfunction "1_1") (pintype "passive"))
      (node (ref "U4") (pin "3") (pinfunction "EN_3") (pintype "passive"))
    )
    (net (code "60") (name "unconnected-(SW2-BT-Pad4)") (class "Default")
      (node (ref "SW2") (pin "4") (pinfunction "BT_4") (pintype "passive+no_connect"))
    )
    (net (code "61") (name "unconnected-(SW2-BT-Pad5)") (class "Default")
      (node (ref "SW2") (pin "5") (pinfunction "BT_5") (pintype "passive+no_connect"))
    )
    (net (code "62") (name "unconnected-(SW3-BT-Pad4)") (class "Default")
      (node (ref "SW3") (pin "4") (pinfunction "BT_4") (pintype "passive+no_connect"))
    )
    (net (code "63") (name "unconnected-(SW3-BT-Pad5)") (class "Default")
      (node (ref "SW3") (pin "5") (pinfunction "BT_5") (pintype "passive+no_connect"))
    )
    (net (code "64") (name "unconnected-(SW5-BT-Pad4)") (class "Default")
      (node (ref "SW5") (pin "4") (pinfunction "BT_4") (pintype "passive+no_connect"))
    )
    (net (code "65") (name "unconnected-(SW5-BT-Pad5)") (class "Default")
      (node (ref "SW5") (pin "5") (pinfunction "BT_5") (pintype "passive+no_connect"))
    )
    (net (code "66") (name "unconnected-(SW6-BT-Pad4)") (class "Default")
      (node (ref "SW6") (pin "4") (pinfunction "BT_4") (pintype "passive+no_connect"))
    )
    (net (code "67") (name "unconnected-(SW6-BT-Pad5)") (class "Default")
      (node (ref "SW6") (pin "5") (pinfunction "BT_5") (pintype "passive+no_connect"))
    )
    (net (code "68") (name "unconnected-(SW7-BT-Pad4)") (class "Default")
      (node (ref "SW7") (pin "4") (pinfunction "BT_4") (pintype "passive+no_connect"))
    )
    (net (code "69") (name "unconnected-(SW7-BT-Pad5)") (class "Default")
      (node (ref "SW7") (pin "5") (pinfunction "BT_5") (pintype "passive+no_connect"))
    )
    (net (code "70") (name "unconnected-(SW8-BT-Pad4)") (class "Default")
      (node (ref "SW8") (pin "4") (pinfunction "BT_4") (pintype "passive+no_connect"))
    )
    (net (code "71") (name "unconnected-(SW8-BT-Pad5)") (class "Default")
      (node (ref "SW8") (pin "5") (pinfunction "BT_5") (pintype "passive+no_connect"))
    )
    (net (code "72") (name "unconnected-(SW10-BT-Pad4)") (class "Default")
      (node (ref "SW10") (pin "4") (pinfunction "BT_4") (pintype "passive+no_connect"))
    )
    (net (code "73") (name "unconnected-(SW10-BT-Pad5)") (class "Default")
      (node (ref "SW10") (pin "5") (pinfunction "BT_5") (pintype "passive+no_connect"))
    )
    (net (code "74") (name "unconnected-(SW11-BT-Pad4)") (class "Default")
      (node (ref "SW11") (pin "4") (pinfunction "BT_4") (pintype "passive+no_connect"))
    )
    (net (code "75") (name "unconnected-(SW11-BT-Pad5)") (class "Default")
      (node (ref "SW11") (pin "5") (pinfunction "BT_5") (pintype "passive+no_connect"))
    )
    (net (code "76") (name "unconnected-(U1-VIN+-Pad1)") (class "Default")
      (node (ref "U1") (pin "1") (pinfunction "VIN+_1") (pintype "passive+no_connect"))
    )
    (net (code "77") (name "unconnected-(U1-VIN--Pad2)") (class "Default")
      (node (ref "U1") (pin "2") (pinfunction "VIN-_2") (pintype "passive+no_connect"))
    )
    (net (code "78") (name "unconnected-(U2-PG-Pad5)") (class "Default")
      (node (ref "U2") (pin "5") (pinfunction "PG_5") (pintype "passive+no_connect"))
    )
    (net (code "79") (name "unconnected-(U4-CLK-Pad20)") (class "Default")
      (node (ref "U4") (pin "20") (pinfunction "CLK_20") (pintype "passive+no_connect"))
    )
    (net (code "80") (name "unconnected-(U4-CMD-Pad19)") (class "Default")
      (node (ref "U4") (pin "19") (pinfunction "CMD_19") (pintype "passive+no_connect"))
    )
    (net (code "81") (name "unconnected-(U4-I35-Pad7)") (class "Default")
      (node (ref "U4") (pin "7") (pinfunction "I35_7") (pintype "passive+no_connect"))
    )
    (net (code "82") (name "unconnected-(U4-IO2*(D)-Pad24)") (class "Default")
      (node (ref "U4") (pin "24") (pinfunction "IO2*(D)_24") (pintype "passive+no_connect"))
    )
    (net (code "83") (name "unconnected-(U4-IO4-Pad26)") (class "Default")
      (node (ref "U4") (pin "26") (pinfunction "IO4_26") (pintype "passive+no_connect"))
    )
    (net (code "84") (name "unconnected-(U4-IO5*(U)-Pad29)") (class "Default")
      (node (ref "U4") (pin "29") (pinfunction "IO5*(U)_29") (pintype "passive+no_connect"))
    )
    (net (code "85") (name "unconnected-(U4-IO19-Pad31)") (class "Default")
      (node (ref "U4") (pin "31") (pinfunction "IO19_31") (pintype "passive+no_connect"))
    )
    (net (code "86") (name "unconnected-(U4-IO23-Pad37)") (class "Default")
      (node (ref "U4") (pin "37") (pinfunction "IO23_37") (pintype "passive+no_connect"))
    )
    (net (code "87") (name "unconnected-(U4-IO25-Pad10)") (class "Default")
      (node (ref "U4") (pin "10") (pinfunction "IO25_10") (pintype "passive+no_connect"))
    )
    (net (code "88") (name "unconnected-(U4-SD0-Pad21)") (class "Default")
      (node (ref "U4") (pin "21") (pinfunction "SD0_21") (pintype "passive+no_connect"))
    )
    (net (code "89") (name "unconnected-(U4-SD1-Pad22)") (class "Default")
      (node (ref "U4") (pin "22") (pinfunction "SD1_22") (pintype "passive+no_connect"))
    )
    (net (code "90") (name "unconnected-(U4-SD2-Pad17)") (class "Default")
      (node (ref "U4") (pin "17") (pinfunction "SD2_17") (pintype "passive+no_connect"))
    )
    (net (code "91") (name "unconnected-(U4-SD3-Pad18)") (class "Default")
      (node (ref "U4") (pin "18") (pinfunction "SD3_18") (pintype "passive+no_connect"))
    )
    (net (code "92") (name "unconnected-(U4-TCK_{slash}_IO13-Pad16)") (class "Default")
      (node (ref "U4") (pin "16") (pinfunction "TCK_/_IO13_16") (pintype "passive+no_connect"))
    )
    (net (code "93") (name "unconnected-(U4-TDI_{slash}_IO12*(D)-Pad14)") (class "Default")
      (node (ref "U4") (pin "14") (pinfunction "TDI_/_IO12*(D)_14") (pintype "passive+no_connect"))
    )
    (net (code "94") (name "unconnected-(U4-TDO_{slash}_IO15*(U)-Pad23)") (class "Default")
      (node (ref "U4") (pin "23") (pinfunction "TDO_/_IO15*(U)_23") (pintype "passive+no_connect"))
    )
    (net (code "95") (name "unconnected-(U4-TMS_{slash}_IO14-Pad13)") (class "Default")
      (node (ref "U4") (pin "13") (pinfunction "TMS_/_IO14_13") (pintype "passive+no_connect"))
    )
    (net (code "96") (name "unconnected-(U5-ANT-Pad6)") (class "Default")
      (node (ref "U5") (pin "6") (pinfunction "ANT_6") (pintype "passive+no_connect"))
    )
  )
)
